# Logomatic.net
KiCad netlist of a schematic drawn in EAGLE
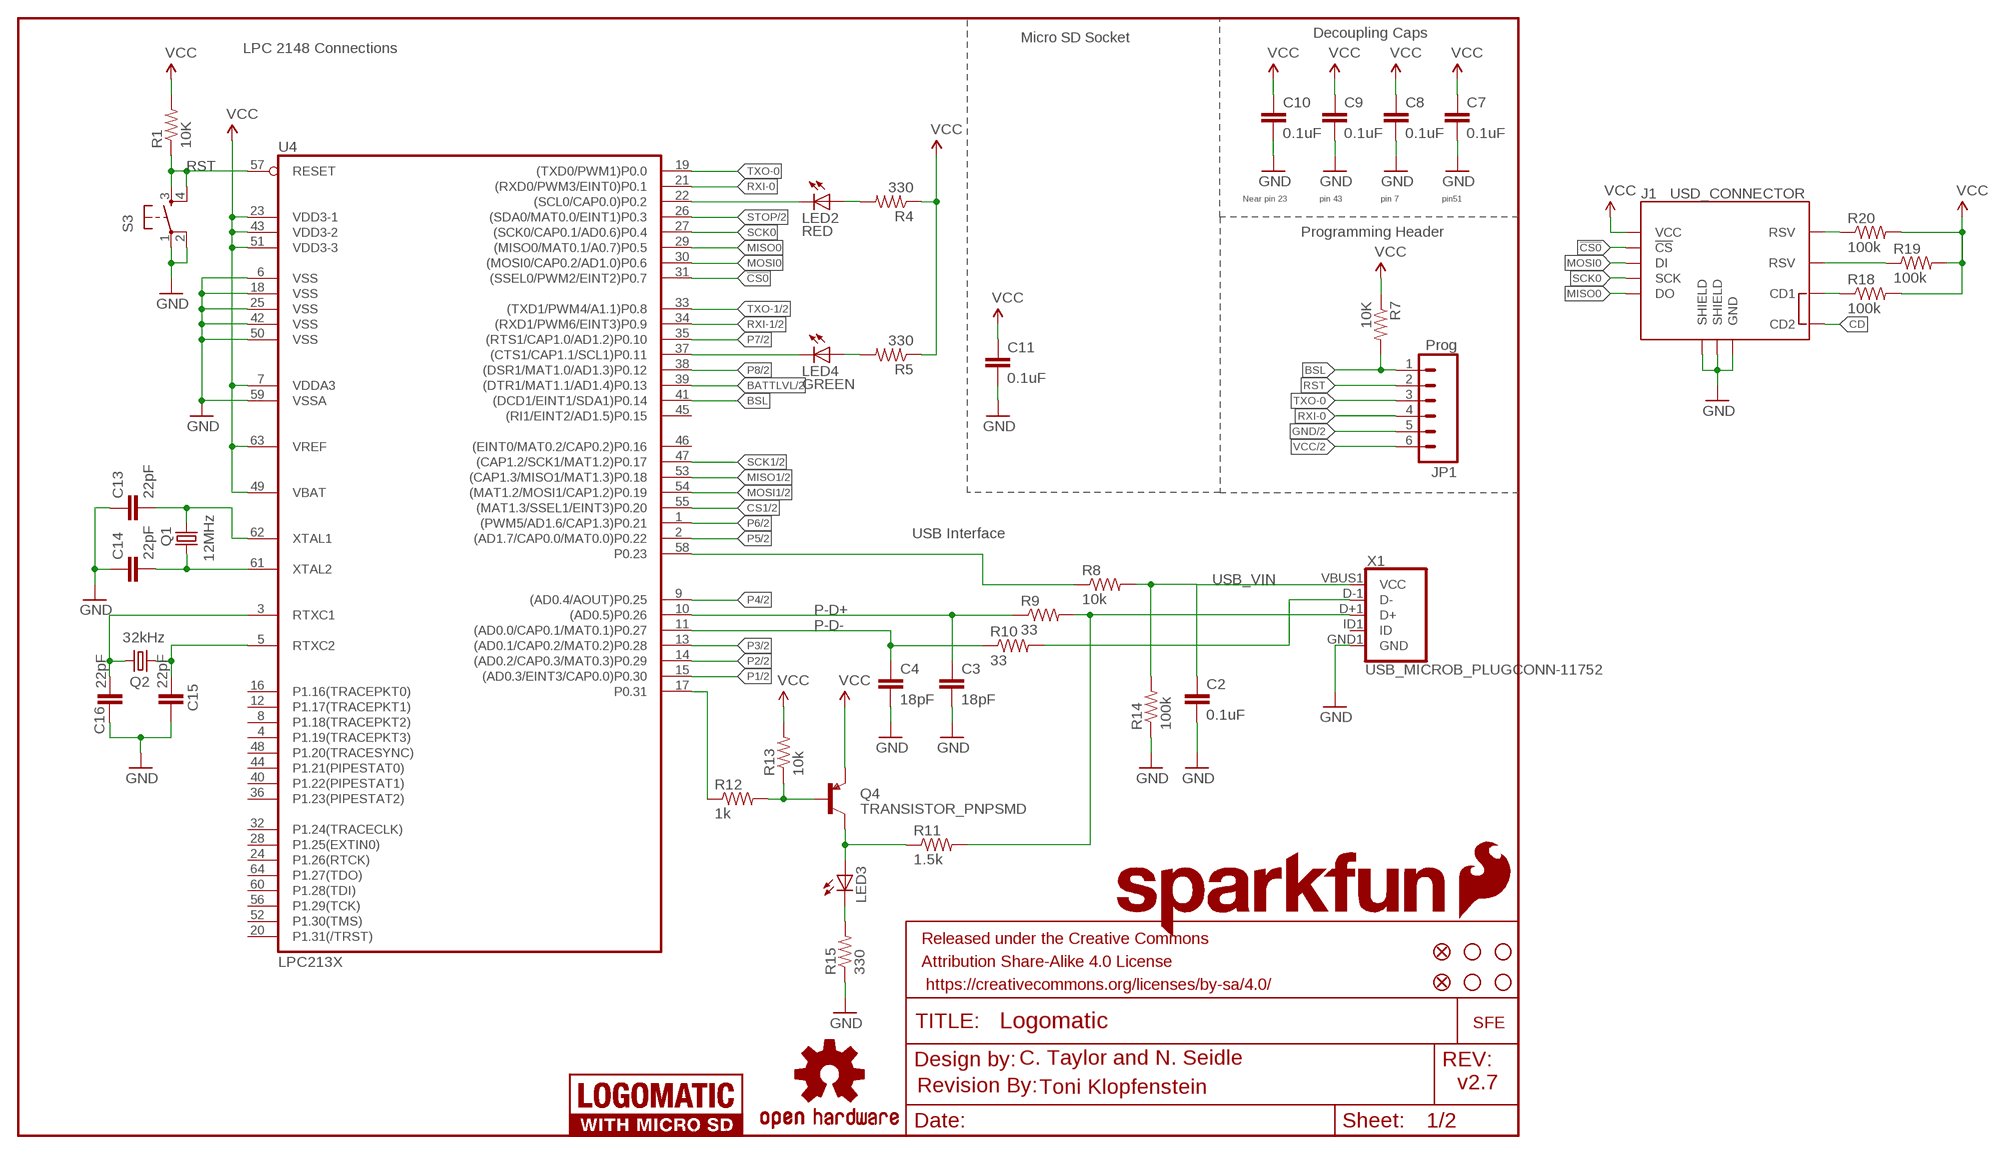
[diagram p0: schematic, sheet 1]
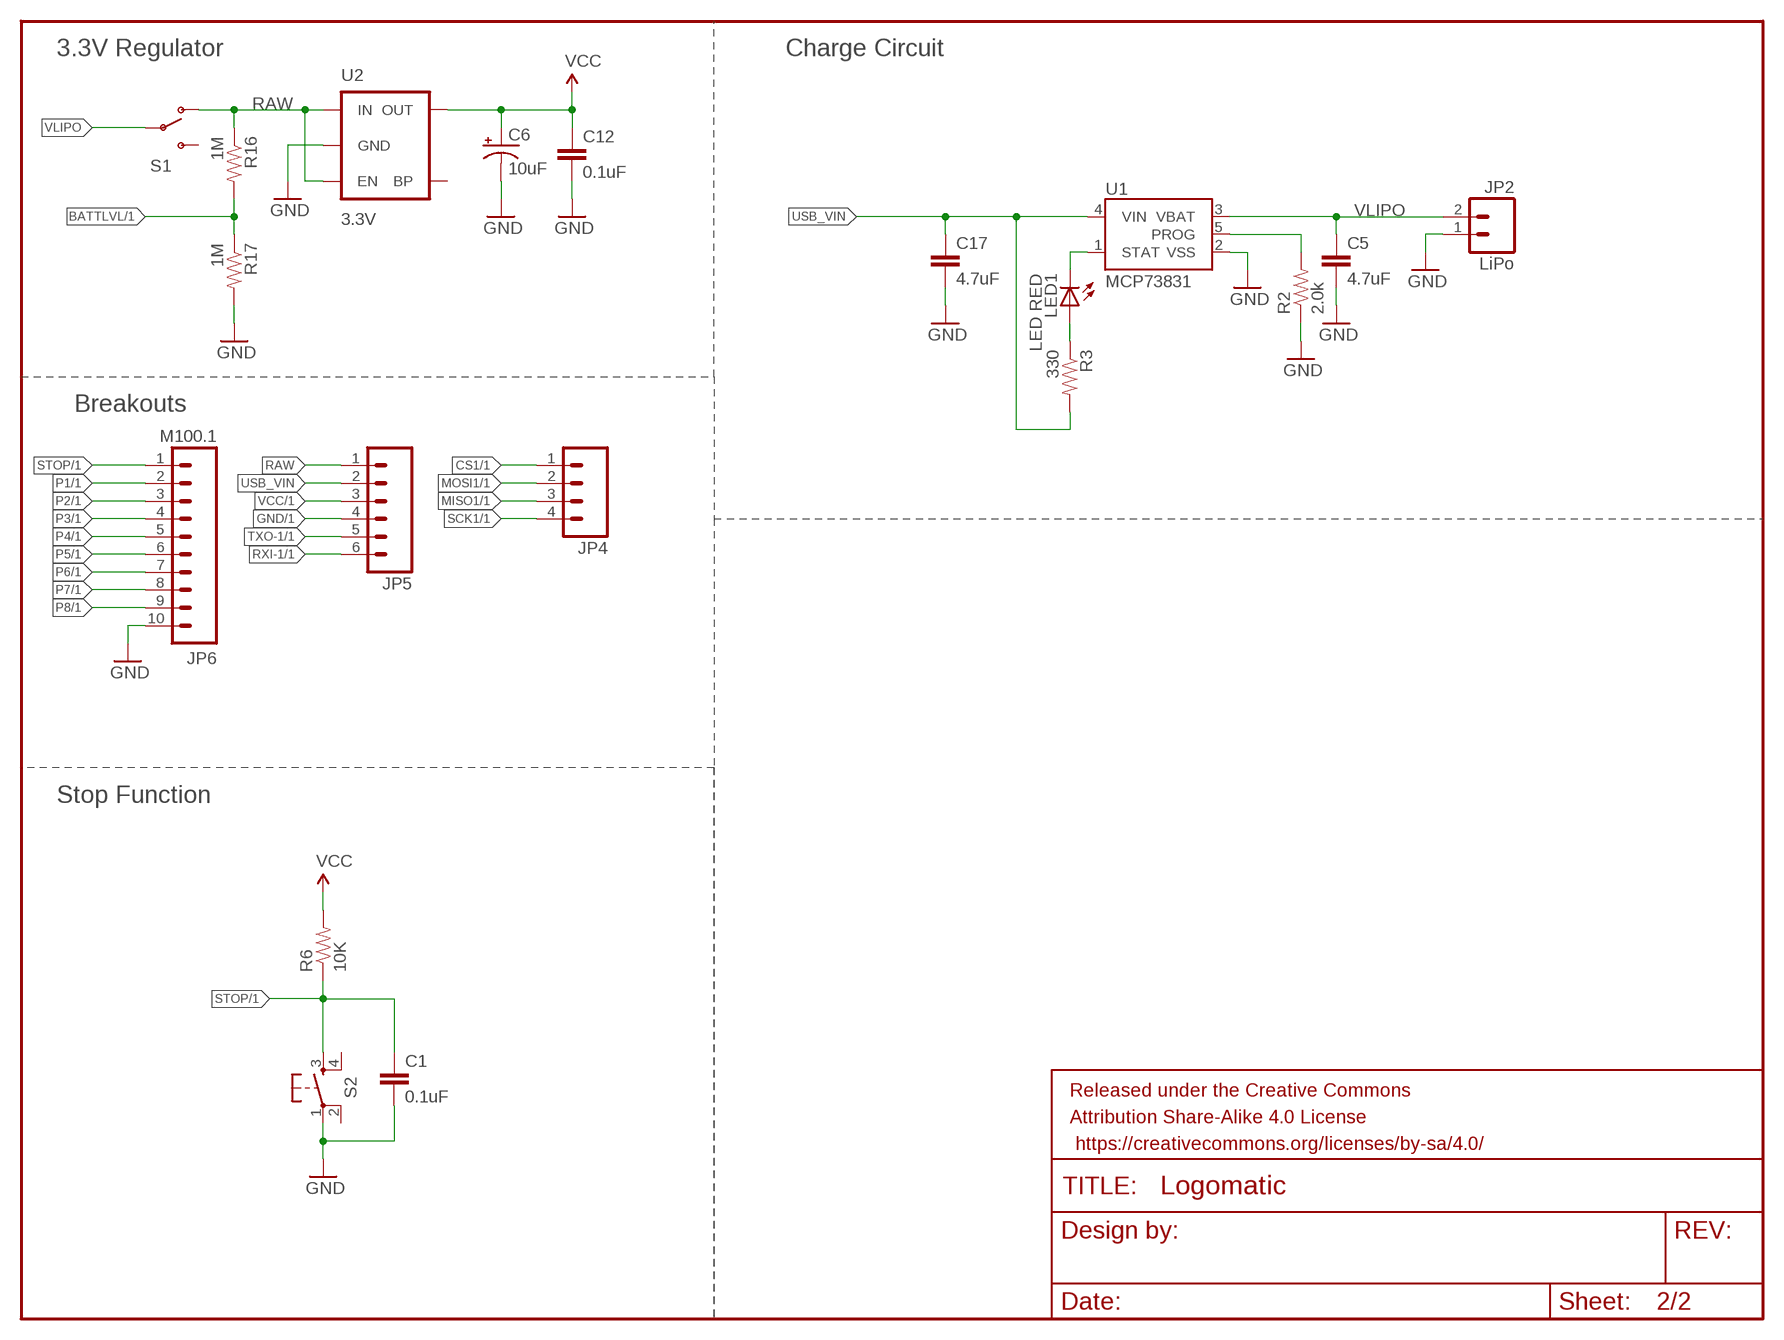
[diagram p1: schematic, sheet 2]

(export (version "E")
  (design (tool "Eeschema 10.0.6"))
  (components
    (comp (ref "C1")
      (value "0.1uF")
      (footprint "eagle-import:0603-CAP")
      (libsource (lib "eagle-import") (part "0.1UF-25V(+80/-20%)(0603)"))
    )
    (comp (ref "C5")
      (value "4.7uF")
      (footprint "eagle-import:0603-CAP")
      (libsource (lib "eagle-import") (part "4.7UF-6.3V-10%(0603)0603"))
    )
    (comp (ref "C6")
      (value "10uF")
      (footprint "eagle-import:EIA3216")
      (libsource (lib "eagle-import") (part "10UF-16V-10%(TANT)"))
    )
    (comp (ref "C12")
      (value "0.1uF")
      (footprint "eagle-import:0603-CAP")
      (libsource (lib "eagle-import") (part "0.1UF-25V(+80/-20%)(0603)"))
    )
    (comp (ref "C17")
      (value "4.7uF")
      (footprint "eagle-import:0603-CAP")
      (libsource (lib "eagle-import") (part "4.7UF-6.3V-10%(0603)0603"))
    )
    (comp (ref "FRAME4")
      (value "FRAME-LETTER")
      (footprint "eagle-import:CREATIVE_COMMONS")
      (libsource (lib "eagle-import") (part "FRAME-LETTER"))
    )
    (comp (ref "JP2")
      (value "LiPo")
      (footprint "eagle-import:JST-2-SMD")
      (libsource (lib "eagle-import") (part "M02-JST-2MM-SMT"))
    )
    (comp (ref "JP4")
      (value "M04PTH")
      (footprint "eagle-import:1X04")
      (libsource (lib "eagle-import") (part "M04PTH"))
    )
    (comp (ref "JP5")
      (value "M06SIP")
      (footprint "eagle-import:1X06")
      (libsource (lib "eagle-import") (part "M06SIP"))
    )
    (comp (ref "JP6")
      (value "M100.1")
      (footprint "eagle-import:1X10")
      (libsource (lib "eagle-import") (part "M10{dblquote}"))
    )
    (comp (ref "LED1")
      (value "LED RED")
      (footprint "eagle-import:LED-0603")
      (libsource (lib "eagle-import") (part "LED-RED0603"))
    )
    (comp (ref "R2")
      (value "2.0k")
      (footprint "eagle-import:0603-RES")
      (libsource (lib "eagle-import") (part "2.0KOHM1/10W5%(0603)"))
    )
    (comp (ref "R3")
      (value "330")
      (footprint "eagle-import:0603-RES")
      (libsource (lib "eagle-import") (part "330OHM1/10W1%(0603)"))
    )
    (comp (ref "R6")
      (value "10K")
      (footprint "eagle-import:0603-RES@1")
      (libsource (lib "eagle-import") (part "10KOHM1/10W1%(0603)0603"))
    )
    (comp (ref "R16")
      (value "1M")
      (footprint "eagle-import:0603-RES@1")
      (libsource (lib "eagle-import") (part "1MOHM1/10W1%(0603)"))
    )
    (comp (ref "R17")
      (value "1M")
      (footprint "eagle-import:0603-RES@1")
      (libsource (lib "eagle-import") (part "1MOHM1/10W1%(0603)"))
    )
    (comp (ref "S1")
      (value "SWITCH-SPSTSMD")
      (footprint "eagle-import:AYZ0202")
      (libsource (lib "eagle-import") (part "SWITCH-SPSTSMD"))
    )
    (comp (ref "S2")
      (value "Stop")
      (footprint "eagle-import:TACTILE_SWITCH_SMD")
      (libsource (lib "eagle-import") (part "TAC_SWITCHSND"))
    )
    (comp (ref "U1")
      (value "MCP73831")
      (footprint "eagle-import:SOT23-5")
      (libsource (lib "eagle-import") (part "MCP73831SMD"))
    )
    (comp (ref "U2")
      (value "3.3V")
      (footprint "eagle-import:SOT23-5")
      (libsource (lib "eagle-import") (part "V_REG_LDOSMD"))
    )
    (comp (ref "C2")
      (value "0.1uF")
      (footprint "eagle-import:0603-CAP")
      (libsource (lib "eagle-import") (part "0.1UF-25V(+80/-20%)(0603)"))
    )
    (comp (ref "C3")
      (value "18pF")
      (footprint "eagle-import:0603-CAP")
      (libsource (lib "eagle-import") (part "18PF-50V-5%(0603)"))
    )
    (comp (ref "C4")
      (value "18pF")
      (footprint "eagle-import:0603-CAP")
      (libsource (lib "eagle-import") (part "18PF-50V-5%(0603)"))
    )
    (comp (ref "C7")
      (value "0.1uF")
      (footprint "eagle-import:0603-CAP")
      (libsource (lib "eagle-import") (part "0.1UF-25V(+80/-20%)(0603)"))
    )
    (comp (ref "C8")
      (value "0.1uF")
      (footprint "eagle-import:0603-CAP")
      (libsource (lib "eagle-import") (part "0.1UF-25V(+80/-20%)(0603)"))
    )
    (comp (ref "C9")
      (value "0.1uF")
      (footprint "eagle-import:0603-CAP")
      (libsource (lib "eagle-import") (part "0.1UF-25V(+80/-20%)(0603)"))
    )
    (comp (ref "C10")
      (value "0.1uF")
      (footprint "eagle-import:0603-CAP")
      (libsource (lib "eagle-import") (part "0.1UF-25V(+80/-20%)(0603)"))
    )
    (comp (ref "C11")
      (value "0.1uF")
      (footprint "eagle-import:0603-CAP")
      (libsource (lib "eagle-import") (part "0.1UF-25V(+80/-20%)(0603)"))
    )
    (comp (ref "C13")
      (value "22pF")
      (footprint "eagle-import:0603-CAP")
      (libsource (lib "eagle-import") (part "22PF-50V-5%(0603)"))
    )
    (comp (ref "C14")
      (value "22pF")
      (footprint "eagle-import:0603-CAP")
      (libsource (lib "eagle-import") (part "22PF-50V-5%(0603)"))
    )
    (comp (ref "C15")
      (value "22pF")
      (footprint "eagle-import:0603-CAP")
      (libsource (lib "eagle-import") (part "22PF-50V-5%(0603)"))
    )
    (comp (ref "C16")
      (value "22pF")
      (footprint "eagle-import:0603-CAP")
      (libsource (lib "eagle-import") (part "22PF-50V-5%(0603)"))
    )
    (comp (ref "FRAME2")
      (value "FRAME-LETTER")
      (footprint "eagle-import:CREATIVE_COMMONS")
      (libsource (lib "eagle-import") (part "FRAME-LETTER"))
    )
    (comp (ref "J1")
      (value "USD_CONNECTOR")
      (footprint "eagle-import:MICRO-SD-SOCKET-PP")
      (libsource (lib "eagle-import") (part "USD_CONNECTOR"))
    )
    (comp (ref "JP1")
      (value "Prog")
      (footprint "eagle-import:1X06")
      (libsource (lib "eagle-import") (part "M06SIP"))
    )
    (comp (ref "LED2")
      (value "RED")
      (footprint "eagle-import:LED-0603")
      (libsource (lib "eagle-import") (part "LED-RED0603"))
    )
    (comp (ref "LED3")
      (value "LED-RED0603")
      (footprint "eagle-import:LED-0603")
      (libsource (lib "eagle-import") (part "LED-RED0603"))
    )
    (comp (ref "LED4")
      (value "GREEN")
      (footprint "eagle-import:LED-0603")
      (libsource (lib "eagle-import") (part "LED-GREEN0603"))
    )
    (comp (ref "LOGO1")
      (value "OSHW-LOGOL")
      (footprint "eagle-import:OSHW-LOGO-L")
      (libsource (lib "eagle-import") (part "OSHW-LOGOL"))
    )
    (comp (ref "LOGO2")
      (value "SFE_LOGO_NAME.1_INCH")
      (footprint "eagle-import:SFE_LOGO_NAME_.1")
      (libsource (lib "eagle-import") (part "SFE_LOGO_NAME.1_INCH"))
    )
    (comp (ref "LOGO3")
      (value "SFE_LOGO_FLAME.4_INCH")
      (footprint "eagle-import:SFE_LOGO_FLAME_.4")
      (libsource (lib "eagle-import") (part "SFE_LOGO_FLAME.4_INCH"))
    )
    (comp (ref "Q1")
      (value "12MHz")
      (footprint "eagle-import:CRYSTAL-SMD-5X3")
      (libsource (lib "eagle-import") (part "SparkFunEagle-6-6-07_CRYSTAL5X3"))
    )
    (comp (ref "Q2")
      (value "32kHz")
      (footprint "eagle-import:CRYSTAL-32KHZ-SMD")
      (libsource (lib "eagle-import") (part "CRYSTAL32-SMD"))
    )
    (comp (ref "Q4")
      (value "TRANSISTOR_PNPSMD")
      (footprint "eagle-import:SOT23-3")
      (libsource (lib "eagle-import") (part "TRANSISTOR_PNPSMD"))
    )
    (comp (ref "R1")
      (value "10K")
      (footprint "eagle-import:0603-RES@1")
      (libsource (lib "eagle-import") (part "10KOHM1/10W1%(0603)0603"))
    )
    (comp (ref "R4")
      (value "330")
      (footprint "eagle-import:0603-RES")
      (libsource (lib "eagle-import") (part "330OHM1/10W1%(0603)"))
    )
    (comp (ref "R5")
      (value "330")
      (footprint "eagle-import:0603-RES")
      (libsource (lib "eagle-import") (part "330OHM1/10W1%(0603)"))
    )
    (comp (ref "R7")
      (value "10K")
      (footprint "eagle-import:0603-RES@1")
      (libsource (lib "eagle-import") (part "10KOHM1/10W1%(0603)0603"))
    )
    (comp (ref "R8")
      (value "10k")
      (footprint "eagle-import:0603-RES@1")
      (libsource (lib "eagle-import") (part "10KOHM1/10W1%(0603)0603"))
    )
    (comp (ref "R9")
      (value "33")
      (footprint "eagle-import:0603-RES")
      (libsource (lib "eagle-import") (part "33OHM1/10W1%(0603)"))
    )
    (comp (ref "R10")
      (value "33")
      (footprint "eagle-import:0603-RES")
      (libsource (lib "eagle-import") (part "33OHM1/10W1%(0603)"))
    )
    (comp (ref "R11")
      (value "1.5k")
      (footprint "eagle-import:0603")
      (libsource (lib "eagle-import") (part "1.5KOHM1/10W1%(0603)"))
    )
    (comp (ref "R12")
      (value "1k")
      (footprint "eagle-import:0603-RES@1")
      (libsource (lib "eagle-import") (part "1KOHM1/10W1%(0603)"))
    )
    (comp (ref "R13")
      (value "10k")
      (footprint "eagle-import:0603-RES@1")
      (libsource (lib "eagle-import") (part "10KOHM1/10W1%(0603)0603"))
    )
    (comp (ref "R14")
      (value "100k")
      (footprint "eagle-import:0603-RES@1")
      (libsource (lib "eagle-import") (part "100KOHM1/10W1%(0603)"))
    )
    (comp (ref "R15")
      (value "330")
      (footprint "eagle-import:0603-RES")
      (libsource (lib "eagle-import") (part "330OHM1/10W1%(0603)"))
    )
    (comp (ref "R18")
      (value "100k")
      (footprint "eagle-import:0603-RES")
      (libsource (lib "eagle-import") (part "100KOHM-1/10W-1%(0603)"))
    )
    (comp (ref "R19")
      (value "100k")
      (footprint "eagle-import:0603-RES")
      (libsource (lib "eagle-import") (part "100KOHM-1/10W-1%(0603)"))
    )
    (comp (ref "R20")
      (value "100k")
      (footprint "eagle-import:0603-RES")
      (libsource (lib "eagle-import") (part "100KOHM-1/10W-1%(0603)"))
    )
    (comp (ref "S3")
      (value "Reset")
      (footprint "eagle-import:TACTILE_SWITCH_SMD")
      (libsource (lib "eagle-import") (part "TAC_SWITCHSND"))
    )
    (comp (ref "U$1")
      (value "FIDUCIAL1X2")
      (footprint "eagle-import:FIDUCIAL-1X2")
      (libsource (lib "eagle-import") (part "FIDUCIAL1X2"))
    )
    (comp (ref "U$2")
      (value "FIDUCIAL1X2")
      (footprint "eagle-import:FIDUCIAL-1X2")
      (libsource (lib "eagle-import") (part "FIDUCIAL1X2"))
    )
    (comp (ref "U$3")
      (value "STAND-OFF")
      (footprint "eagle-import:STAND-OFF")
      (libsource (lib "eagle-import") (part "STAND-OFF"))
    )
    (comp (ref "U$4")
      (value "STAND-OFF")
      (footprint "eagle-import:STAND-OFF")
      (libsource (lib "eagle-import") (part "STAND-OFF"))
    )
    (comp (ref "U$5")
      (value "STAND-OFF")
      (footprint "eagle-import:STAND-OFF")
      (libsource (lib "eagle-import") (part "STAND-OFF"))
    )
    (comp (ref "U$6")
      (value "LOGOMATIC_LOGO")
      (footprint "eagle-import:LOGOMATIC_LOGO")
      (libsource (lib "eagle-import") (part "LOGOMATIC_LOGO"))
    )
    (comp (ref "U$7")
      (value "LOGO-SFESK")
      (footprint "eagle-import:SFE-LOGO-FLAME")
      (libsource (lib "eagle-import") (part "LOGO-SFESK"))
    )
    (comp (ref "U$8")
      (value "STAND-OFF")
      (footprint "eagle-import:STAND-OFF")
      (libsource (lib "eagle-import") (part "STAND-OFF"))
    )
    (comp (ref "U$10")
      (value "REVISION")
      (footprint "eagle-import:REVISION")
      (libsource (lib "eagle-import") (part "REVISION"))
    )
    (comp (ref "U4")
      (value "LPC213X")
      (footprint "eagle-import:SQFP-S-10X10-64")
      (libsource (lib "eagle-import") (part "LPC213X"))
    )
    (comp (ref "X1")
      (value "USB_MICROB_PLUGCONN-11752")
      (footprint "eagle-import:USB-B-MICRO-SMD_V03")
      (libsource (lib "eagle-import") (part "USB_MICROB_PLUGCONN-11752"))
    )
  )
  (nets
    (net (code "1") (name "BATTLVL") (class "Default")
      (node (ref "R16") (pin "2") (pinfunction "2_2") (pintype "passive"))
      (node (ref "R17") (pin "1") (pinfunction "1_1") (pintype "passive"))
      (node (ref "U4") (pin "39") (pinfunction "(DTR1/MAT1.1/AD1.4)P0.13_39") (pintype "bidirectional"))
    )
    (net (code "2") (name "BSL") (class "Default")
      (node (ref "JP1") (pin "1") (pinfunction "1_1") (pintype "passive"))
      (node (ref "R7") (pin "2") (pinfunction "2_2") (pintype "passive"))
      (node (ref "U4") (pin "41") (pinfunction "(DCD1/EINT1/SDA1)P0.14_41") (pintype "bidirectional"))
    )
    (net (code "3") (name "CD") (class "Default")
      (node (ref "J1") (pin "CD2") (pinfunction "CD2_CD2") (pintype "bidirectional"))
    )
    (net (code "4") (name "CS1") (class "Default")
      (node (ref "JP4") (pin "1") (pinfunction "1_1") (pintype "passive"))
      (node (ref "U4") (pin "55") (pinfunction "(MAT1.3/SSEL1/EINT3)P0.20_55") (pintype "bidirectional"))
    )
    (net (code "5") (name "GND") (class "Default")
      (node (ref "C1") (pin "2") (pinfunction "2_2") (pintype "passive"))
      (node (ref "C10") (pin "2") (pinfunction "2_2") (pintype "passive"))
      (node (ref "C11") (pin "2") (pinfunction "2_2") (pintype "passive"))
      (node (ref "C12") (pin "2") (pinfunction "2_2") (pintype "passive"))
      (node (ref "C13") (pin "1") (pinfunction "1_1") (pintype "passive"))
      (node (ref "C14") (pin "1") (pinfunction "1_1") (pintype "passive"))
      (node (ref "C15") (pin "1") (pinfunction "1_1") (pintype "passive"))
      (node (ref "C16") (pin "1") (pinfunction "1_1") (pintype "passive"))
      (node (ref "C17") (pin "2") (pinfunction "2_2") (pintype "passive"))
      (node (ref "C2") (pin "2") (pinfunction "2_2") (pintype "passive"))
      (node (ref "C3") (pin "2") (pinfunction "2_2") (pintype "passive"))
      (node (ref "C4") (pin "2") (pinfunction "2_2") (pintype "passive"))
      (node (ref "C5") (pin "2") (pinfunction "2_2") (pintype "passive"))
      (node (ref "C6") (pin "C") (pinfunction "-_C") (pintype "passive"))
      (node (ref "C7") (pin "2") (pinfunction "2_2") (pintype "passive"))
      (node (ref "C8") (pin "2") (pinfunction "2_2") (pintype "passive"))
      (node (ref "C9") (pin "2") (pinfunction "2_2") (pintype "passive"))
      (node (ref "J1") (pin "GND") (pinfunction "GND_GND") (pintype "bidirectional"))
      (node (ref "J1") (pin "GND1") (pinfunction "SHIELD_GND1") (pintype "bidirectional"))
      (node (ref "J1") (pin "GND3") (pinfunction "SHIELD_GND3") (pintype "bidirectional"))
      (node (ref "JP1") (pin "5") (pinfunction "5_5") (pintype "passive"))
      (node (ref "JP2") (pin "1") (pinfunction "1_1") (pintype "passive"))
      (node (ref "JP5") (pin "4") (pinfunction "4_4") (pintype "passive"))
      (node (ref "JP6") (pin "10") (pinfunction "10_10") (pintype "passive"))
      (node (ref "R14") (pin "1") (pinfunction "1_1") (pintype "passive"))
      (node (ref "R15") (pin "1") (pinfunction "1_1") (pintype "passive"))
      (node (ref "R17") (pin "2") (pinfunction "2_2") (pintype "passive"))
      (node (ref "R2") (pin "1") (pinfunction "1_1") (pintype "passive"))
      (node (ref "S2") (pin "1") (pinfunction "1_1") (pintype "passive"))
      (node (ref "S3") (pin "1") (pinfunction "1_1") (pintype "passive"))
      (node (ref "S3") (pin "2") (pinfunction "2_2") (pintype "passive"))
      (node (ref "U1") (pin "2") (pinfunction "VSS_2") (pintype "power_in"))
      (node (ref "U2") (pin "2") (pinfunction "GND_2") (pintype "input"))
      (node (ref "U4") (pin "18") (pinfunction "VSS_18") (pintype "power_in"))
      (node (ref "U4") (pin "25") (pinfunction "VSS_25") (pintype "power_in"))
      (node (ref "U4") (pin "42") (pinfunction "VSS_42") (pintype "power_in"))
      (node (ref "U4") (pin "50") (pinfunction "VSS_50") (pintype "power_in"))
      (node (ref "U4") (pin "59") (pinfunction "VSSA_59") (pintype "power_in"))
      (node (ref "U4") (pin "6") (pinfunction "VSS_6") (pintype "power_in"))
      (node (ref "X1") (pin "GND1") (pinfunction "GND_GND1") (pintype "bidirectional"))
    )
    (net (code "6") (name "MISO0") (class "Default")
      (node (ref "J1") (pin "DO") (pinfunction "DO_DO") (pintype "bidirectional"))
      (node (ref "U4") (pin "29") (pinfunction "(MISO0/MAT0.1/A0.7)P0.5_29") (pintype "bidirectional"))
    )
    (net (code "7") (name "MISO1") (class "Default")
      (node (ref "JP4") (pin "3") (pinfunction "3_3") (pintype "passive"))
      (node (ref "U4") (pin "53") (pinfunction "(CAP1.3/MISO1/MAT1.3)P0.18_53") (pintype "bidirectional"))
    )
    (net (code "8") (name "MOSI0") (class "Default")
      (node (ref "J1") (pin "DI") (pinfunction "DI_DI") (pintype "bidirectional"))
      (node (ref "U4") (pin "30") (pinfunction "(MOSI0/CAP0.2/AD1.0)P0.6_30") (pintype "bidirectional"))
    )
    (net (code "9") (name "MOSI1") (class "Default")
      (node (ref "JP4") (pin "2") (pinfunction "2_2") (pintype "passive"))
      (node (ref "U4") (pin "54") (pinfunction "(MAT1.2/MOSI1/CAP1.2)P0.19_54") (pintype "bidirectional"))
    )
    (net (code "10") (name "Net-(J1-PadCD1)") (class "Default")
      (node (ref "J1") (pin "CD1") (pinfunction "CD1_CD1") (pintype "bidirectional"))
      (node (ref "R18") (pin "1") (pinfunction "1_1") (pintype "passive"))
    )
    (net (code "11") (name "Net-(J1-RSV-PadRSV1)") (class "Default")
      (node (ref "J1") (pin "RSV1") (pinfunction "RSV_RSV1") (pintype "bidirectional"))
      (node (ref "R20") (pin "1") (pinfunction "1_1") (pintype "passive"))
    )
    (net (code "12") (name "Net-(J1-RSV-PadRSV2)") (class "Default")
      (node (ref "J1") (pin "RSV2") (pinfunction "RSV_RSV2") (pintype "bidirectional"))
      (node (ref "R19") (pin "1") (pinfunction "1_1") (pintype "passive"))
    )
    (net (code "13") (name "Net-(LED1-PadA)") (class "Default")
      (node (ref "LED1") (pin "A") (pinfunction "A_A") (pintype "passive"))
      (node (ref "R3") (pin "1") (pinfunction "1_1") (pintype "passive"))
    )
    (net (code "14") (name "Net-(LED2-PadA)") (class "Default")
      (node (ref "LED2") (pin "A") (pinfunction "A_A") (pintype "passive"))
      (node (ref "R4") (pin "2") (pinfunction "2_2") (pintype "passive"))
    )
    (net (code "15") (name "Net-(LED3-PadC)") (class "Default")
      (node (ref "LED3") (pin "C") (pinfunction "C_C") (pintype "passive"))
      (node (ref "R15") (pin "2") (pinfunction "2_2") (pintype "passive"))
    )
    (net (code "16") (name "Net-(LED4-PadA)") (class "Default")
      (node (ref "LED4") (pin "A") (pinfunction "A_A") (pintype "passive"))
      (node (ref "R5") (pin "2") (pinfunction "2_2") (pintype "passive"))
    )
    (net (code "17") (name "Net-(Q1-2)") (class "Default")
      (node (ref "C13") (pin "2") (pinfunction "2_2") (pintype "passive"))
      (node (ref "Q1") (pin "3") (pinfunction "2_3") (pintype "passive"))
      (node (ref "U4") (pin "62") (pinfunction "XTAL1_62") (pintype "input"))
    )
    (net (code "18") (name "Net-(Q2-1)") (class "Default")
      (node (ref "C15") (pin "2") (pinfunction "2_2") (pintype "passive"))
      (node (ref "Q2") (pin "X1") (pinfunction "1_X1") (pintype "passive"))
      (node (ref "U4") (pin "5") (pinfunction "RTXC2_5") (pintype "output"))
    )
    (net (code "19") (name "Net-(Q2-2)") (class "Default")
      (node (ref "C16") (pin "2") (pinfunction "2_2") (pintype "passive"))
      (node (ref "Q2") (pin "X2") (pinfunction "2_X2") (pintype "passive"))
      (node (ref "U4") (pin "3") (pinfunction "RTXC1_3") (pintype "input"))
    )
    (net (code "20") (name "Net-(Q4-B)") (class "Default")
      (node (ref "Q4") (pin "1") (pinfunction "B_1") (pintype "passive"))
      (node (ref "R12") (pin "2") (pinfunction "2_2") (pintype "passive"))
      (node (ref "R13") (pin "1") (pinfunction "1_1") (pintype "passive"))
    )
    (net (code "21") (name "Net-(Q4-C)") (class "Default")
      (node (ref "LED3") (pin "A") (pinfunction "A_A") (pintype "passive"))
      (node (ref "Q4") (pin "3") (pinfunction "C_3") (pintype "passive"))
      (node (ref "R11") (pin "1") (pinfunction "1_1") (pintype "passive"))
    )
    (net (code "22") (name "Net-(U1-PROG)") (class "Default")
      (node (ref "R2") (pin "2") (pinfunction "2_2") (pintype "passive"))
      (node (ref "U1") (pin "5") (pinfunction "PROG_5") (pintype "input"))
    )
    (net (code "23") (name "Net-(U1-STAT)") (class "Default")
      (node (ref "LED1") (pin "C") (pinfunction "C_C") (pintype "passive"))
      (node (ref "U1") (pin "1") (pinfunction "STAT_1") (pintype "output"))
    )
    (net (code "24") (name "Net-(U4-(CTS1{slash}CAP1.1{slash}SCL1)P0.11)") (class "Default")
      (node (ref "LED4") (pin "C") (pinfunction "C_C") (pintype "passive"))
      (node (ref "U4") (pin "37") (pinfunction "(CTS1/CAP1.1/SCL1)P0.11_37") (pintype "bidirectional"))
    )
    (net (code "25") (name "Net-(U4-(SCL0{slash}CAP0.0)P0.2)") (class "Default")
      (node (ref "LED2") (pin "C") (pinfunction "C_C") (pintype "passive"))
      (node (ref "U4") (pin "22") (pinfunction "(SCL0/CAP0.0)P0.2_22") (pintype "bidirectional"))
    )
    (net (code "26") (name "Net-(U4-P0.23)") (class "Default")
      (node (ref "R8") (pin "1") (pinfunction "1_1") (pintype "passive"))
      (node (ref "U4") (pin "58") (pinfunction "P0.23_58") (pintype "bidirectional"))
    )
    (net (code "27") (name "Net-(U4-P0.31)") (class "Default")
      (node (ref "R12") (pin "1") (pinfunction "1_1") (pintype "passive"))
      (node (ref "U4") (pin "17") (pinfunction "P0.31_17") (pintype "output"))
    )
    (net (code "28") (name "Net-(U4-XTAL2)") (class "Default")
      (node (ref "C14") (pin "2") (pinfunction "2_2") (pintype "passive"))
      (node (ref "Q1") (pin "1") (pinfunction "1_1") (pintype "passive"))
      (node (ref "U4") (pin "61") (pinfunction "XTAL2_61") (pintype "output"))
    )
    (net (code "29") (name "Net-(X1-D+)") (class "Default")
      (node (ref "R11") (pin "2") (pinfunction "2_2") (pintype "passive"))
      (node (ref "R9") (pin "2") (pinfunction "2_2") (pintype "passive"))
      (node (ref "X1") (pin "D+1") (pinfunction "D+_D+1") (pintype "bidirectional"))
    )
    (net (code "30") (name "Net-(X1-D-)") (class "Default")
      (node (ref "R10") (pin "2") (pinfunction "2_2") (pintype "passive"))
      (node (ref "X1") (pin "D-1") (pinfunction "D-_D-1") (pintype "bidirectional"))
    )
    (net (code "31") (name "P-D+") (class "Default")
      (node (ref "C3") (pin "1") (pinfunction "1_1") (pintype "passive"))
      (node (ref "R9") (pin "1") (pinfunction "1_1") (pintype "passive"))
      (node (ref "U4") (pin "10") (pinfunction "(AD0.5)P0.26_10") (pintype "bidirectional"))
    )
    (net (code "32") (name "P-D-") (class "Default")
      (node (ref "C4") (pin "1") (pinfunction "1_1") (pintype "passive"))
      (node (ref "R10") (pin "1") (pinfunction "1_1") (pintype "passive"))
      (node (ref "U4") (pin "11") (pinfunction "(AD0.0/CAP0.1/MAT0.1)P0.27_11") (pintype "bidirectional"))
    )
    (net (code "33") (name "P1") (class "Default")
      (node (ref "JP6") (pin "2") (pinfunction "2_2") (pintype "passive"))
      (node (ref "U4") (pin "15") (pinfunction "(AD0.3/EINT3/CAP0.0)P0.30_15") (pintype "bidirectional"))
    )
    (net (code "34") (name "P2") (class "Default")
      (node (ref "JP6") (pin "3") (pinfunction "3_3") (pintype "passive"))
      (node (ref "U4") (pin "14") (pinfunction "(AD0.2/CAP0.3/MAT0.3)P0.29_14") (pintype "bidirectional"))
    )
    (net (code "35") (name "P3") (class "Default")
      (node (ref "JP6") (pin "4") (pinfunction "4_4") (pintype "passive"))
      (node (ref "U4") (pin "13") (pinfunction "(AD0.1/CAP0.2/MAT0.2)P0.28_13") (pintype "bidirectional"))
    )
    (net (code "36") (name "P4") (class "Default")
      (node (ref "JP6") (pin "5") (pinfunction "5_5") (pintype "passive"))
      (node (ref "U4") (pin "9") (pinfunction "(AD0.4/AOUT)P0.25_9") (pintype "bidirectional"))
    )
    (net (code "37") (name "P5") (class "Default")
      (node (ref "JP6") (pin "6") (pinfunction "6_6") (pintype "passive"))
      (node (ref "U4") (pin "2") (pinfunction "(AD1.7/CAP0.0/MAT0.0)P0.22_2") (pintype "bidirectional"))
    )
    (net (code "38") (name "P6") (class "Default")
      (node (ref "JP6") (pin "7") (pinfunction "7_7") (pintype "passive"))
      (node (ref "U4") (pin "1") (pinfunction "(PWM5/AD1.6/CAP1.3)P0.21_1") (pintype "bidirectional"))
    )
    (net (code "39") (name "P7") (class "Default")
      (node (ref "JP6") (pin "8") (pinfunction "8_8") (pintype "passive"))
      (node (ref "U4") (pin "35") (pinfunction "(RTS1/CAP1.0/AD1.2)P0.10_35") (pintype "bidirectional"))
    )
    (net (code "40") (name "P8") (class "Default")
      (node (ref "JP6") (pin "9") (pinfunction "9_9") (pintype "passive"))
      (node (ref "U4") (pin "38") (pinfunction "(DSR1/MAT1.0/AD1.3)P0.12_38") (pintype "bidirectional"))
    )
    (net (code "41") (name "RAW") (class "Default")
      (node (ref "JP5") (pin "1") (pinfunction "1_1") (pintype "passive"))
      (node (ref "R16") (pin "1") (pinfunction "1_1") (pintype "passive"))
      (node (ref "S1") (pin "1") (pinfunction "O_1") (pintype "passive"))
      (node (ref "U2") (pin "1") (pinfunction "IN_1") (pintype "input"))
      (node (ref "U2") (pin "3") (pinfunction "EN_3") (pintype "input"))
    )
    (net (code "42") (name "RST") (class "Default")
      (node (ref "JP1") (pin "2") (pinfunction "2_2") (pintype "passive"))
      (node (ref "R1") (pin "1") (pinfunction "1_1") (pintype "passive"))
      (node (ref "S3") (pin "3") (pinfunction "3_3") (pintype "passive"))
      (node (ref "S3") (pin "4") (pinfunction "4_4") (pintype "passive"))
      (node (ref "U4") (pin "57") (pinfunction "RESET_57") (pintype "input"))
    )
    (net (code "43") (name "RXI-0") (class "Default")
      (node (ref "JP1") (pin "4") (pinfunction "4_4") (pintype "passive"))
      (node (ref "U4") (pin "21") (pinfunction "(RXD0/PWM3/EINT0)P0.1_21") (pintype "bidirectional"))
    )
    (net (code "44") (name "RXI-1") (class "Default")
      (node (ref "JP5") (pin "6") (pinfunction "6_6") (pintype "passive"))
      (node (ref "U4") (pin "34") (pinfunction "(RXD1/PWM6/EINT3)P0.9_34") (pintype "bidirectional"))
    )
    (net (code "45") (name "SCK0") (class "Default")
      (node (ref "J1") (pin "SCLK") (pinfunction "SCK_SCLK") (pintype "bidirectional"))
      (node (ref "U4") (pin "27") (pinfunction "(SCK0/CAP0.1/AD0.6)P0.4_27") (pintype "bidirectional"))
    )
    (net (code "46") (name "SCK1") (class "Default")
      (node (ref "JP4") (pin "4") (pinfunction "4_4") (pintype "passive"))
      (node (ref "U4") (pin "47") (pinfunction "(CAP1.2/SCK1/MAT1.2)P0.17_47") (pintype "bidirectional"))
    )
    (net (code "47") (name "STOP") (class "Default")
      (node (ref "C1") (pin "1") (pinfunction "1_1") (pintype "passive"))
      (node (ref "JP6") (pin "1") (pinfunction "1_1") (pintype "passive"))
      (node (ref "R6") (pin "1") (pinfunction "1_1") (pintype "passive"))
      (node (ref "S2") (pin "3") (pinfunction "3_3") (pintype "passive"))
      (node (ref "U4") (pin "26") (pinfunction "(SDA0/MAT0.0/EINT1)P0.3_26") (pintype "bidirectional"))
    )
    (net (code "48") (name "TXO-0") (class "Default")
      (node (ref "JP1") (pin "3") (pinfunction "3_3") (pintype "passive"))
      (node (ref "U4") (pin "19") (pinfunction "(TXD0/PWM1)P0.0_19") (pintype "bidirectional"))
    )
    (net (code "49") (name "TXO-1") (class "Default")
      (node (ref "JP5") (pin "5") (pinfunction "5_5") (pintype "passive"))
      (node (ref "U4") (pin "33") (pinfunction "(TXD1/PWM4/A1.1)P0.8_33") (pintype "bidirectional"))
    )
    (net (code "50") (name "USB_VIN") (class "Default")
      (node (ref "C17") (pin "1") (pinfunction "1_1") (pintype "passive"))
      (node (ref "C2") (pin "1") (pinfunction "1_1") (pintype "passive"))
      (node (ref "JP5") (pin "2") (pinfunction "2_2") (pintype "passive"))
      (node (ref "R14") (pin "2") (pinfunction "2_2") (pintype "passive"))
      (node (ref "R3") (pin "2") (pinfunction "2_2") (pintype "passive"))
      (node (ref "R8") (pin "2") (pinfunction "2_2") (pintype "passive"))
      (node (ref "U1") (pin "4") (pinfunction "VIN_4") (pintype "power_in"))
      (node (ref "X1") (pin "VBUS1") (pinfunction "VCC_VBUS1") (pintype "bidirectional"))
    )
    (net (code "51") (name "VCC") (class "Default")
      (node (ref "C10") (pin "1") (pinfunction "1_1") (pintype "passive"))
      (node (ref "C11") (pin "1") (pinfunction "1_1") (pintype "passive"))
      (node (ref "C12") (pin "1") (pinfunction "1_1") (pintype "passive"))
      (node (ref "C6") (pin "A") (pinfunction "+_A") (pintype "passive"))
      (node (ref "C7") (pin "1") (pinfunction "1_1") (pintype "passive"))
      (node (ref "C8") (pin "1") (pinfunction "1_1") (pintype "passive"))
      (node (ref "C9") (pin "1") (pinfunction "1_1") (pintype "passive"))
      (node (ref "J1") (pin "VCC") (pinfunction "VCC_VCC") (pintype "bidirectional"))
      (node (ref "JP1") (pin "6") (pinfunction "6_6") (pintype "passive"))
      (node (ref "JP5") (pin "3") (pinfunction "3_3") (pintype "passive"))
      (node (ref "Q4") (pin "2") (pinfunction "E_2") (pintype "passive"))
      (node (ref "R1") (pin "2") (pinfunction "2_2") (pintype "passive"))
      (node (ref "R13") (pin "2") (pinfunction "2_2") (pintype "passive"))
      (node (ref "R18") (pin "2") (pinfunction "2_2") (pintype "passive"))
      (node (ref "R19") (pin "2") (pinfunction "2_2") (pintype "passive"))
      (node (ref "R20") (pin "2") (pinfunction "2_2") (pintype "passive"))
      (node (ref "R4") (pin "1") (pinfunction "1_1") (pintype "passive"))
      (node (ref "R5") (pin "1") (pinfunction "1_1") (pintype "passive"))
      (node (ref "R6") (pin "2") (pinfunction "2_2") (pintype "passive"))
      (node (ref "R7") (pin "1") (pinfunction "1_1") (pintype "passive"))
      (node (ref "U2") (pin "5") (pinfunction "OUT_5") (pintype "passive"))
      (node (ref "U4") (pin "23") (pinfunction "VDD3-1_23") (pintype "power_in"))
      (node (ref "U4") (pin "43") (pinfunction "VDD3-2_43") (pintype "power_in"))
      (node (ref "U4") (pin "49") (pinfunction "VBAT_49") (pintype "power_in"))
      (node (ref "U4") (pin "51") (pinfunction "VDD3-3_51") (pintype "power_in"))
      (node (ref "U4") (pin "63") (pinfunction "VREF_63") (pintype "input"))
      (node (ref "U4") (pin "7") (pinfunction "VDDA3_7") (pintype "power_in"))
    )
    (net (code "52") (name "VLIPO") (class "Default")
      (node (ref "C5") (pin "1") (pinfunction "1_1") (pintype "passive"))
      (node (ref "JP2") (pin "2") (pinfunction "2_2") (pintype "passive"))
      (node (ref "S1") (pin "2") (pinfunction "P_2") (pintype "passive"))
      (node (ref "U1") (pin "3") (pinfunction "VBAT_3") (pintype "power_in"))
    )
    (net (code "53") (name "unconnected-(S1-S-Pad3)") (class "Default")
      (node (ref "S1") (pin "3") (pinfunction "S_3") (pintype "passive"))
    )
    (net (code "54") (name "unconnected-(S2-Pad2)") (class "Default")
      (node (ref "S2") (pin "2") (pinfunction "2_2") (pintype "passive"))
    )
    (net (code "55") (name "unconnected-(S2-Pad4)") (class "Default")
      (node (ref "S2") (pin "4") (pinfunction "4_4") (pintype "passive"))
    )
    (net (code "56") (name "unconnected-(U2-BP-Pad4)") (class "Default")
      (node (ref "U2") (pin "4") (pinfunction "BP_4") (pintype "input"))
    )
    (net (code "57") (name "unconnected-(U4-(EINT0{slash}MAT0.2{slash}CAP0.2)P0.16-Pad46)") (class "Default")
      (node (ref "U4") (pin "46") (pinfunction "(EINT0/MAT0.2/CAP0.2)P0.16_46") (pintype "bidirectional"))
    )
    (net (code "58") (name "unconnected-(U4-(RI1{slash}EINT2{slash}AD1.5)P0.15-Pad45)") (class "Default")
      (node (ref "U4") (pin "45") (pinfunction "(RI1/EINT2/AD1.5)P0.15_45") (pintype "bidirectional"))
    )
    (net (code "59") (name "unconnected-(U4-P1.16(TRACEPKT0)-Pad16)") (class "Default")
      (node (ref "U4") (pin "16") (pinfunction "P1.16(TRACEPKT0)_16") (pintype "bidirectional"))
    )
    (net (code "60") (name "unconnected-(U4-P1.17(TRACEPKT1)-Pad12)") (class "Default")
      (node (ref "U4") (pin "12") (pinfunction "P1.17(TRACEPKT1)_12") (pintype "bidirectional"))
    )
    (net (code "61") (name "unconnected-(U4-P1.18(TRACEPKT2)-Pad8)") (class "Default")
      (node (ref "U4") (pin "8") (pinfunction "P1.18(TRACEPKT2)_8") (pintype "bidirectional"))
    )
    (net (code "62") (name "unconnected-(U4-P1.19(TRACEPKT3)-Pad4)") (class "Default")
      (node (ref "U4") (pin "4") (pinfunction "P1.19(TRACEPKT3)_4") (pintype "bidirectional"))
    )
    (net (code "63") (name "unconnected-(U4-P1.20(TRACESYNC)-Pad48)") (class "Default")
      (node (ref "U4") (pin "48") (pinfunction "P1.20(TRACESYNC)_48") (pintype "bidirectional"))
    )
    (net (code "64") (name "unconnected-(U4-P1.21(PIPESTAT0)-Pad44)") (class "Default")
      (node (ref "U4") (pin "44") (pinfunction "P1.21(PIPESTAT0)_44") (pintype "bidirectional"))
    )
    (net (code "65") (name "unconnected-(U4-P1.22(PIPESTAT1)-Pad40)") (class "Default")
      (node (ref "U4") (pin "40") (pinfunction "P1.22(PIPESTAT1)_40") (pintype "bidirectional"))
    )
    (net (code "66") (name "unconnected-(U4-P1.23(PIPESTAT2)-Pad36)") (class "Default")
      (node (ref "U4") (pin "36") (pinfunction "P1.23(PIPESTAT2)_36") (pintype "bidirectional"))
    )
    (net (code "67") (name "unconnected-(U4-P1.24(TRACECLK)-Pad32)") (class "Default")
      (node (ref "U4") (pin "32") (pinfunction "P1.24(TRACECLK)_32") (pintype "bidirectional"))
    )
    (net (code "68") (name "unconnected-(U4-P1.25(EXTIN0)-Pad28)") (class "Default")
      (node (ref "U4") (pin "28") (pinfunction "P1.25(EXTIN0)_28") (pintype "bidirectional"))
    )
    (net (code "69") (name "unconnected-(U4-P1.26(RTCK)-Pad24)") (class "Default")
      (node (ref "U4") (pin "24") (pinfunction "P1.26(RTCK)_24") (pintype "bidirectional"))
    )
    (net (code "70") (name "unconnected-(U4-P1.27(TDO)-Pad64)") (class "Default")
      (node (ref "U4") (pin "64") (pinfunction "P1.27(TDO)_64") (pintype "bidirectional"))
    )
    (net (code "71") (name "unconnected-(U4-P1.28(TDI)-Pad60)") (class "Default")
      (node (ref "U4") (pin "60") (pinfunction "P1.28(TDI)_60") (pintype "bidirectional"))
    )
    (net (code "72") (name "unconnected-(U4-P1.29(TCK)-Pad56)") (class "Default")
      (node (ref "U4") (pin "56") (pinfunction "P1.29(TCK)_56") (pintype "bidirectional"))
    )
    (net (code "73") (name "unconnected-(U4-P1.30(TMS)-Pad52)") (class "Default")
      (node (ref "U4") (pin "52") (pinfunction "P1.30(TMS)_52") (pintype "bidirectional"))
    )
    (net (code "74") (name "unconnected-(U4-P1.31({slash}TRST)-Pad20)") (class "Default")
      (node (ref "U4") (pin "20") (pinfunction "P1.31(/TRST)_20") (pintype "bidirectional"))
    )
    (net (code "75") (name "unconnected-(X1-ID-PadID1)") (class "Default")
      (node (ref "X1") (pin "ID1") (pinfunction "ID_ID1") (pintype "bidirectional"))
    )
    (net (code "76") (name "~{CS0}") (class "Default")
      (node (ref "J1") (pin "CS") (pinfunction "~{CS}_CS") (pintype "bidirectional"))
      (node (ref "U4") (pin "31") (pinfunction "(SSEL0/PWM2/EINT2)P0.7_31") (pintype "bidirectional"))
    )
  )
)
